# Unused.net
KiCad netlist of a schematic drawn in Altium Designer
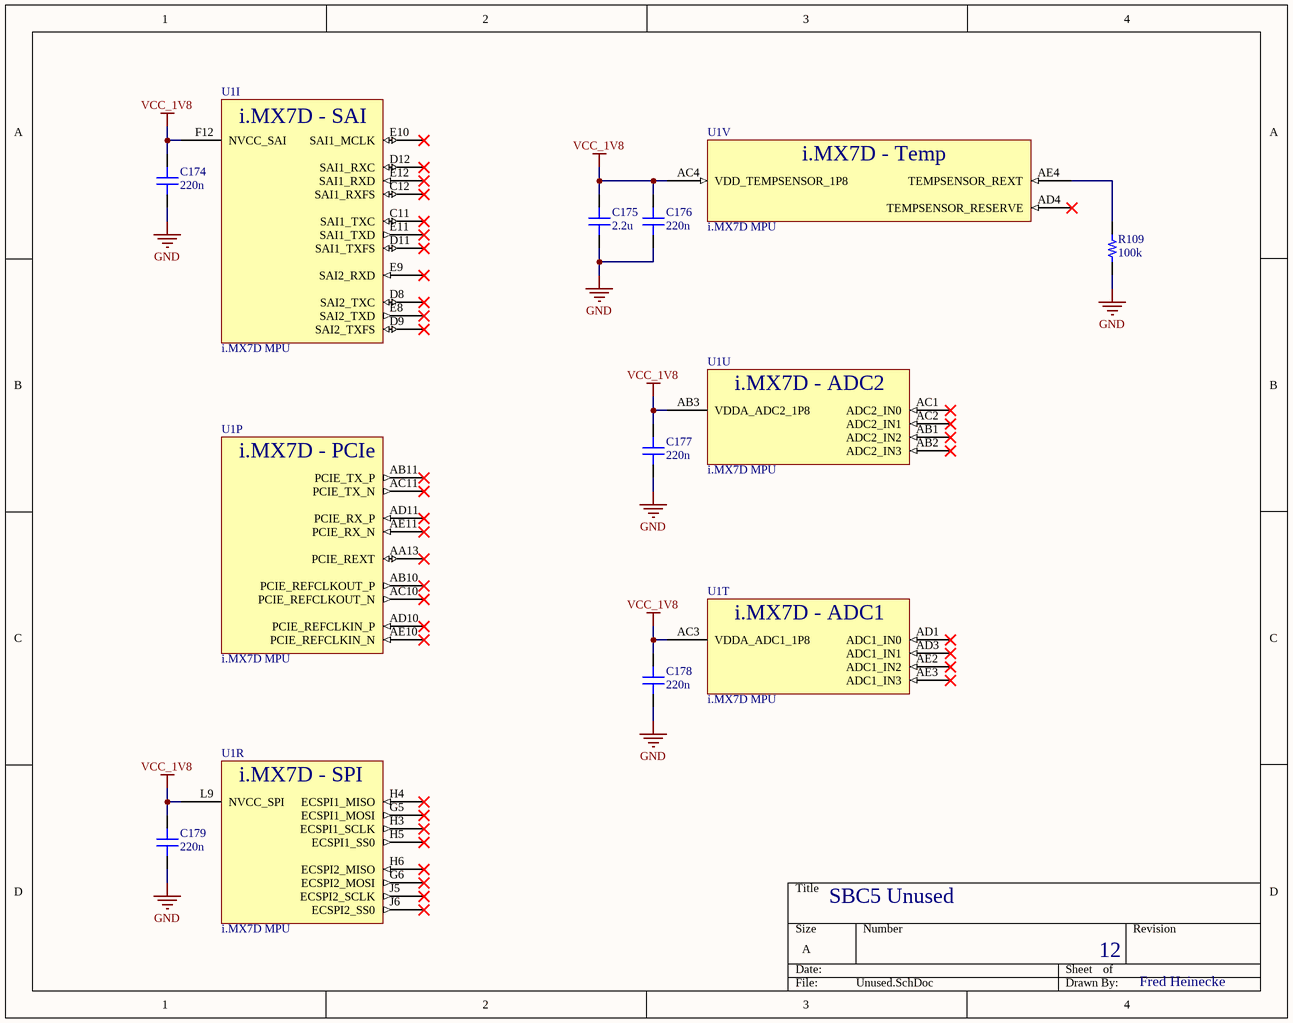
[diagram p0: Unused.SchDoc]

(export (version "E")
  (design (tool "Eeschema 10.0.6"))
  (components
    (comp (ref "C174")
      (value "220n")
      (footprint "C0201")
      (description "Cap Ceramic Monolithic 0.22uF 16VDC 10% SMD Paper T/R")
      (fields
        (field (name "MANUFACTURER") "Murata")
        (field (name "MANUFACTURER PART NUMBER") "GRM033R61C224KE14D")
      )
      (libsource (lib "SBC5") (part "GRM033R61C224KE14D"))
    )
    (comp (ref "C175")
      (value "2.2u")
      (footprint "C0402")
      (description "TAIYO YUDEN         LMK105BJ225MV-F            CERAMIC CAPACITOR, 2.2UF, 10V, X5R, 20%, 0402")
      (fields
        (field (name "MANUFACTURER") "Taiyo Yuden")
        (field (name "MANUFACTURER PART NUMBER") "LMK105BJ225MV-F")
      )
      (libsource (lib "SBC5") (part "LMK105BJ225MV-F"))
    )
    (comp (ref "C176")
      (value "220n")
      (footprint "C0201")
      (description "Cap Ceramic Monolithic 0.22uF 16VDC 10% SMD Paper T/R")
      (fields
        (field (name "MANUFACTURER") "Murata")
        (field (name "MANUFACTURER PART NUMBER") "GRM033R61C224KE14D")
      )
      (libsource (lib "SBC5") (part "GRM033R61C224KE14D"))
    )
    (comp (ref "C177")
      (value "220n")
      (footprint "C0201")
      (description "Cap Ceramic Monolithic 0.22uF 16VDC 10% SMD Paper T/R")
      (fields
        (field (name "MANUFACTURER") "Murata")
        (field (name "MANUFACTURER PART NUMBER") "GRM033R61C224KE14D")
      )
      (libsource (lib "SBC5") (part "GRM033R61C224KE14D"))
    )
    (comp (ref "C178")
      (value "220n")
      (footprint "C0201")
      (description "Cap Ceramic Monolithic 0.22uF 16VDC 10% SMD Paper T/R")
      (fields
        (field (name "MANUFACTURER") "Murata")
        (field (name "MANUFACTURER PART NUMBER") "GRM033R61C224KE14D")
      )
      (libsource (lib "SBC5") (part "GRM033R61C224KE14D"))
    )
    (comp (ref "C179")
      (value "220n")
      (footprint "C0201")
      (description "Cap Ceramic Monolithic 0.22uF 16VDC 10% SMD Paper T/R")
      (fields
        (field (name "MANUFACTURER") "Murata")
        (field (name "MANUFACTURER PART NUMBER") "GRM033R61C224KE14D")
      )
      (libsource (lib "SBC5") (part "GRM033R61C224KE14D"))
    )
    (comp (ref "R109")
      (value "100k")
      (footprint "R0201")
      (description "PANASONIC - ERJ1GNF1003C - RES, 100K, 1%, 0.05W, 0201, THICK FILM")
      (fields
        (field (name "MANUFACTURER") "Panasonic")
        (field (name "MANUFACTURER PART NUMBER") "ERJ-1GNF1003C")
      )
      (libsource (lib "SBC5") (part "ERJ-1GNF1003C"))
    )
    (comp (ref "U1")
      (value "i.MX7D MPU")
      (footprint "BGA541C75P25X25_1900X1900X140")
      (description "Heterogeneous Multicore Processing Architecture")
      (fields
        (field (name "MANUFACTURER") "NXP Freescale")
        (field (name "MANUFACTURER PART NUMBER") "MCIMX7D2DVM12SD")
      )
      (libsource (lib "SBC5") (part "MCIMX7D2DVM12SD"))
    )
  )
  (nets
    (net (code "1") (name "GND") (class "Default")
      (node (ref "C174") (pin "1") (pinfunction "1_1") (pintype "passive"))
      (node (ref "C175") (pin "1") (pinfunction "1_1") (pintype "passive"))
      (node (ref "C176") (pin "1") (pinfunction "1_1") (pintype "passive"))
      (node (ref "C177") (pin "1") (pinfunction "1_1") (pintype "passive"))
      (node (ref "C178") (pin "1") (pinfunction "1_1") (pintype "passive"))
      (node (ref "C179") (pin "1") (pinfunction "1_1") (pintype "passive"))
      (node (ref "R109") (pin "1") (pinfunction "1_1") (pintype "passive"))
    )
    (net (code "2") (name "Net-(U1V-TEMPSENSOR_REXT)") (class "Default")
      (node (ref "R109") (pin "2") (pinfunction "2_2") (pintype "passive"))
      (node (ref "U1") (pin "AE4") (pinfunction "TEMPSENSOR_REXT_AE4") (pintype "input"))
    )
    (net (code "3") (name "VCC_1V8") (class "Default")
      (node (ref "C174") (pin "2") (pinfunction "2_2") (pintype "passive"))
      (node (ref "C175") (pin "2") (pinfunction "2_2") (pintype "passive"))
      (node (ref "C176") (pin "2") (pinfunction "2_2") (pintype "passive"))
      (node (ref "C177") (pin "2") (pinfunction "2_2") (pintype "passive"))
      (node (ref "C178") (pin "2") (pinfunction "2_2") (pintype "passive"))
      (node (ref "C179") (pin "2") (pinfunction "2_2") (pintype "passive"))
      (node (ref "U1") (pin "AB3") (pinfunction "VDDA_ADC2_1P8_AB3") (pintype "power_in"))
      (node (ref "U1") (pin "AC3") (pinfunction "VDDA_ADC1_1P8_AC3") (pintype "power_in"))
      (node (ref "U1") (pin "AC4") (pinfunction "VDD_TEMPSENSOR_1P8_AC4") (pintype "input"))
      (node (ref "U1") (pin "F12") (pinfunction "NVCC_SAI_F12") (pintype "power_in"))
      (node (ref "U1") (pin "L9") (pinfunction "NVCC_SPI_L9") (pintype "power_in"))
    )
    (net (code "4") (name "unconnected-(U1I-SAI1_MCLK-PadE10)") (class "Default")
      (node (ref "U1") (pin "E10") (pinfunction "SAI1_MCLK_E10") (pintype "bidirectional+no_connect"))
    )
    (net (code "5") (name "unconnected-(U1I-SAI1_RXC-PadD12)") (class "Default")
      (node (ref "U1") (pin "D12") (pinfunction "SAI1_RXC_D12") (pintype "bidirectional+no_connect"))
    )
    (net (code "6") (name "unconnected-(U1I-SAI1_RXD-PadE12)") (class "Default")
      (node (ref "U1") (pin "E12") (pinfunction "SAI1_RXD_E12") (pintype "input+no_connect"))
    )
    (net (code "7") (name "unconnected-(U1I-SAI1_RXFS-PadC12)") (class "Default")
      (node (ref "U1") (pin "C12") (pinfunction "SAI1_RXFS_C12") (pintype "bidirectional+no_connect"))
    )
    (net (code "8") (name "unconnected-(U1I-SAI1_TXC-PadC11)") (class "Default")
      (node (ref "U1") (pin "C11") (pinfunction "SAI1_TXC_C11") (pintype "bidirectional+no_connect"))
    )
    (net (code "9") (name "unconnected-(U1I-SAI1_TXD-PadE11)") (class "Default")
      (node (ref "U1") (pin "E11") (pinfunction "SAI1_TXD_E11") (pintype "output+no_connect"))
    )
    (net (code "10") (name "unconnected-(U1I-SAI1_TXFS-PadD11)") (class "Default")
      (node (ref "U1") (pin "D11") (pinfunction "SAI1_TXFS_D11") (pintype "bidirectional+no_connect"))
    )
    (net (code "11") (name "unconnected-(U1I-SAI2_RXD-PadE9)") (class "Default")
      (node (ref "U1") (pin "E9") (pinfunction "SAI2_RXD_E9") (pintype "input+no_connect"))
    )
    (net (code "12") (name "unconnected-(U1I-SAI2_TXC-PadD8)") (class "Default")
      (node (ref "U1") (pin "D8") (pinfunction "SAI2_TXC_D8") (pintype "bidirectional+no_connect"))
    )
    (net (code "13") (name "unconnected-(U1I-SAI2_TXD-PadE8)") (class "Default")
      (node (ref "U1") (pin "E8") (pinfunction "SAI2_TXD_E8") (pintype "output+no_connect"))
    )
    (net (code "14") (name "unconnected-(U1I-SAI2_TXFS-PadD9)") (class "Default")
      (node (ref "U1") (pin "D9") (pinfunction "SAI2_TXFS_D9") (pintype "bidirectional+no_connect"))
    )
    (net (code "15") (name "unconnected-(U1P-PCIE_REFCLKIN_N-PadAE10)") (class "Default")
      (node (ref "U1") (pin "AE10") (pinfunction "PCIE_REFCLKIN_N_AE10") (pintype "input+no_connect"))
    )
    (net (code "16") (name "unconnected-(U1P-PCIE_REFCLKIN_P-PadAD10)") (class "Default")
      (node (ref "U1") (pin "AD10") (pinfunction "PCIE_REFCLKIN_P_AD10") (pintype "input+no_connect"))
    )
    (net (code "17") (name "unconnected-(U1P-PCIE_REFCLKOUT_N-PadAC10)") (class "Default")
      (node (ref "U1") (pin "AC10") (pinfunction "PCIE_REFCLKOUT_N_AC10") (pintype "output+no_connect"))
    )
    (net (code "18") (name "unconnected-(U1P-PCIE_REFCLKOUT_P-PadAB10)") (class "Default")
      (node (ref "U1") (pin "AB10") (pinfunction "PCIE_REFCLKOUT_P_AB10") (pintype "output+no_connect"))
    )
    (net (code "19") (name "unconnected-(U1P-PCIE_REXT-PadAA13)") (class "Default")
      (node (ref "U1") (pin "AA13") (pinfunction "PCIE_REXT_AA13") (pintype "bidirectional+no_connect"))
    )
    (net (code "20") (name "unconnected-(U1P-PCIE_RX_N-PadAE11)") (class "Default")
      (node (ref "U1") (pin "AE11") (pinfunction "PCIE_RX_N_AE11") (pintype "input+no_connect"))
    )
    (net (code "21") (name "unconnected-(U1P-PCIE_RX_P-PadAD11)") (class "Default")
      (node (ref "U1") (pin "AD11") (pinfunction "PCIE_RX_P_AD11") (pintype "input+no_connect"))
    )
    (net (code "22") (name "unconnected-(U1P-PCIE_TX_N-PadAC11)") (class "Default")
      (node (ref "U1") (pin "AC11") (pinfunction "PCIE_TX_N_AC11") (pintype "output+no_connect"))
    )
    (net (code "23") (name "unconnected-(U1P-PCIE_TX_P-PadAB11)") (class "Default")
      (node (ref "U1") (pin "AB11") (pinfunction "PCIE_TX_P_AB11") (pintype "output+no_connect"))
    )
    (net (code "24") (name "unconnected-(U1R-ECSPI1_MISO-PadH4)") (class "Default")
      (node (ref "U1") (pin "H4") (pinfunction "ECSPI1_MISO_H4") (pintype "input+no_connect"))
    )
    (net (code "25") (name "unconnected-(U1R-ECSPI1_MOSI-PadG5)") (class "Default")
      (node (ref "U1") (pin "G5") (pinfunction "ECSPI1_MOSI_G5") (pintype "output+no_connect"))
    )
    (net (code "26") (name "unconnected-(U1R-ECSPI1_SCLK-PadH3)") (class "Default")
      (node (ref "U1") (pin "H3") (pinfunction "ECSPI1_SCLK_H3") (pintype "output+no_connect"))
    )
    (net (code "27") (name "unconnected-(U1R-ECSPI1_SS0-PadH5)") (class "Default")
      (node (ref "U1") (pin "H5") (pinfunction "ECSPI1_SS0_H5") (pintype "output+no_connect"))
    )
    (net (code "28") (name "unconnected-(U1R-ECSPI2_MISO-PadH6)") (class "Default")
      (node (ref "U1") (pin "H6") (pinfunction "ECSPI2_MISO_H6") (pintype "input+no_connect"))
    )
    (net (code "29") (name "unconnected-(U1R-ECSPI2_MOSI-PadG6)") (class "Default")
      (node (ref "U1") (pin "G6") (pinfunction "ECSPI2_MOSI_G6") (pintype "output+no_connect"))
    )
    (net (code "30") (name "unconnected-(U1R-ECSPI2_SCLK-PadJ5)") (class "Default")
      (node (ref "U1") (pin "J5") (pinfunction "ECSPI2_SCLK_J5") (pintype "output+no_connect"))
    )
    (net (code "31") (name "unconnected-(U1R-ECSPI2_SS0-PadJ6)") (class "Default")
      (node (ref "U1") (pin "J6") (pinfunction "ECSPI2_SS0_J6") (pintype "output+no_connect"))
    )
    (net (code "32") (name "unconnected-(U1T-ADC1_IN0-PadAD1)") (class "Default")
      (node (ref "U1") (pin "AD1") (pinfunction "ADC1_IN0_AD1") (pintype "input+no_connect"))
    )
    (net (code "33") (name "unconnected-(U1T-ADC1_IN1-PadAD3)") (class "Default")
      (node (ref "U1") (pin "AD3") (pinfunction "ADC1_IN1_AD3") (pintype "input+no_connect"))
    )
    (net (code "34") (name "unconnected-(U1T-ADC1_IN2-PadAE2)") (class "Default")
      (node (ref "U1") (pin "AE2") (pinfunction "ADC1_IN2_AE2") (pintype "input+no_connect"))
    )
    (net (code "35") (name "unconnected-(U1T-ADC1_IN3-PadAE3)") (class "Default")
      (node (ref "U1") (pin "AE3") (pinfunction "ADC1_IN3_AE3") (pintype "input+no_connect"))
    )
    (net (code "36") (name "unconnected-(U1U-ADC2_IN0-PadAC1)") (class "Default")
      (node (ref "U1") (pin "AC1") (pinfunction "ADC2_IN0_AC1") (pintype "input+no_connect"))
    )
    (net (code "37") (name "unconnected-(U1U-ADC2_IN1-PadAC2)") (class "Default")
      (node (ref "U1") (pin "AC2") (pinfunction "ADC2_IN1_AC2") (pintype "input+no_connect"))
    )
    (net (code "38") (name "unconnected-(U1U-ADC2_IN2-PadAB1)") (class "Default")
      (node (ref "U1") (pin "AB1") (pinfunction "ADC2_IN2_AB1") (pintype "input+no_connect"))
    )
    (net (code "39") (name "unconnected-(U1U-ADC2_IN3-PadAB2)") (class "Default")
      (node (ref "U1") (pin "AB2") (pinfunction "ADC2_IN3_AB2") (pintype "input+no_connect"))
    )
    (net (code "40") (name "unconnected-(U1V-TEMPSENSOR_RESERVE-PadAD4)") (class "Default")
      (node (ref "U1") (pin "AD4") (pinfunction "TEMPSENSOR_RESERVE_AD4") (pintype "input+no_connect"))
    )
  )
)
